# 7660.net
KiCad netlist of a schematic drawn in EAGLE
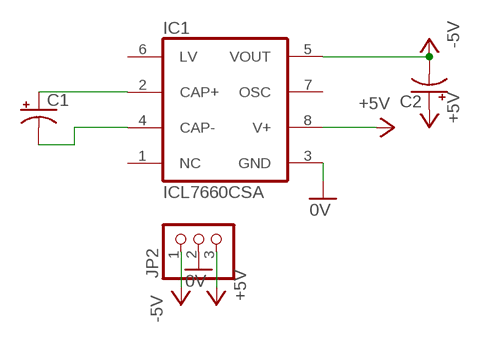
[diagram p0: schematic, sheet 1]

(export (version "E")
  (design (tool "Eeschema 10.0.6"))
  (components
    (comp (ref "C1")
      (value "CPOL-USE2,5-6E")
      (footprint "eagle-import:E2,5-6E")
      (libsource (lib "eagle-import") (part "CPOL-USE2,5-6E"))
    )
    (comp (ref "C2")
      (value "CPOL-USE2,5-6E")
      (footprint "eagle-import:E2,5-6E")
      (libsource (lib "eagle-import") (part "CPOL-USE2,5-6E"))
    )
    (comp (ref "IC1")
      (value "ICL7660CSA")
      (footprint "eagle-import:SO08")
      (fields (field (name "MF") "MAXIM"))
      (libsource (lib "eagle-import") (part "ICL7660CSA"))
    )
    (comp (ref "JP2")
      (value "PINHD-1X3")
      (footprint "eagle-import:1X03")
      (libsource (lib "eagle-import") (part "PINHD-1X3"))
    )
  )
  (nets
    (net (code "1") (name "+5V") (class "Default")
      (node (ref "C2") (pin "+") (pinfunction "+_+") (pintype "passive"))
      (node (ref "IC1") (pin "8") (pinfunction "V+_8") (pintype "power_in"))
      (node (ref "JP2") (pin "3") (pinfunction "3_3") (pintype "passive"))
    )
    (net (code "2") (name "-5V") (class "Default")
      (node (ref "C2") (pin "-") (pinfunction "-_-") (pintype "passive"))
      (node (ref "IC1") (pin "5") (pinfunction "VOUT_5") (pintype "output"))
      (node (ref "JP2") (pin "1") (pinfunction "1_1") (pintype "passive"))
    )
    (net (code "3") (name "0V") (class "Default")
      (node (ref "IC1") (pin "3") (pinfunction "GND_3") (pintype "power_in"))
      (node (ref "JP2") (pin "2") (pinfunction "2_2") (pintype "passive"))
    )
    (net (code "4") (name "Net-(IC1-CAP+)") (class "Default")
      (node (ref "C1") (pin "+") (pinfunction "+_+") (pintype "passive"))
      (node (ref "IC1") (pin "2") (pinfunction "CAP+_2") (pintype "passive"))
    )
    (net (code "5") (name "Net-(IC1-CAP-)") (class "Default")
      (node (ref "C1") (pin "-") (pinfunction "-_-") (pintype "passive"))
      (node (ref "IC1") (pin "4") (pinfunction "CAP-_4") (pintype "passive"))
    )
    (net (code "6") (name "unconnected-(IC1-LV-Pad6)") (class "Default")
      (node (ref "IC1") (pin "6") (pinfunction "LV_6") (pintype "passive"))
    )
    (net (code "7") (name "unconnected-(IC1-NC-Pad1)") (class "Default")
      (node (ref "IC1") (pin "1") (pinfunction "NC_1") (pintype "no_connect"))
    )
    (net (code "8") (name "unconnected-(IC1-OSC-Pad7)") (class "Default")
      (node (ref "IC1") (pin "7") (pinfunction "OSC_7") (pintype "output"))
    )
  )
)
